# LCDController.net
KiCad netlist of a schematic drawn in EAGLE
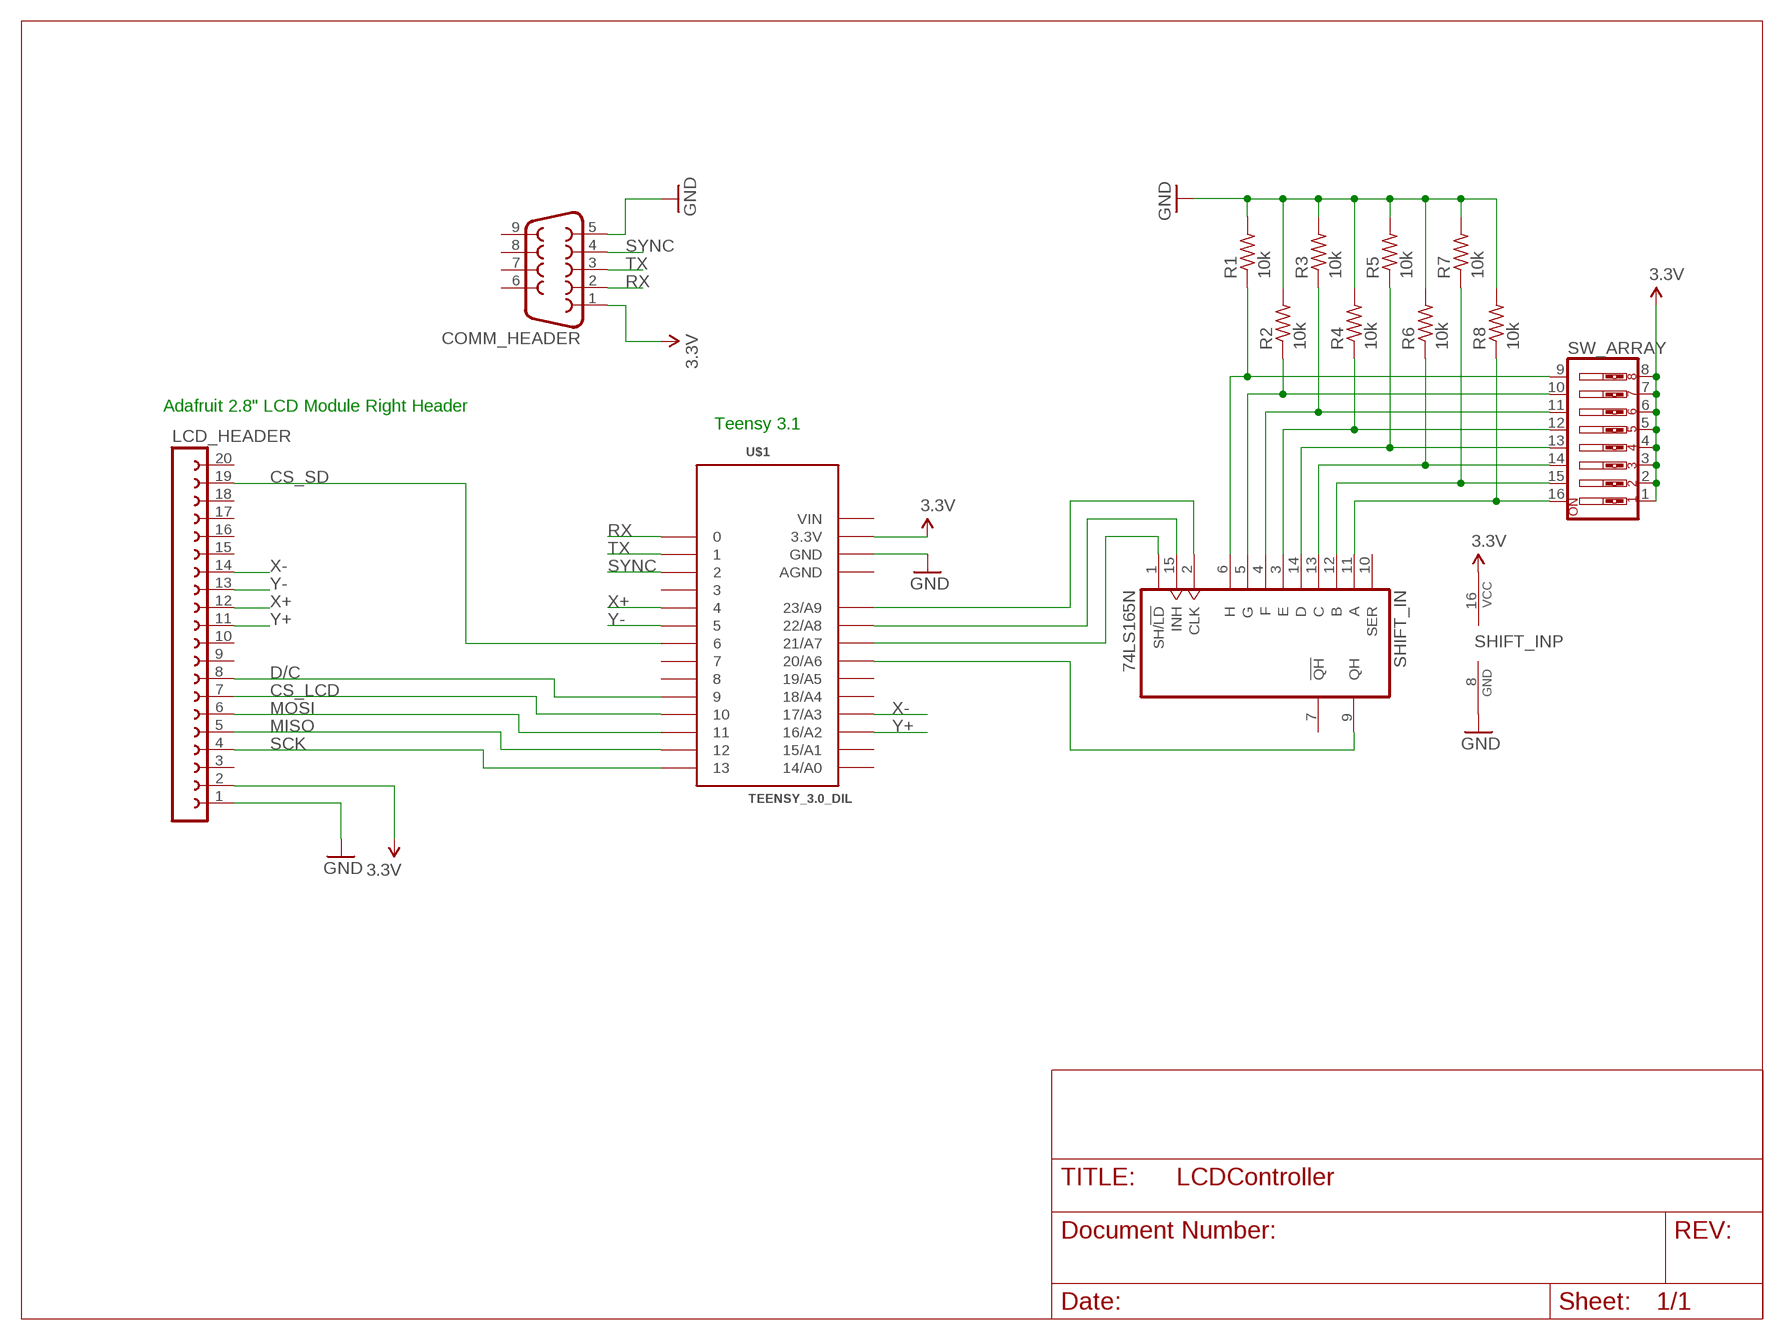
[diagram p0: schematic, sheet 1]

(export (version "E")
  (design (tool "Eeschema 10.0.6"))
  (components
    (comp (ref "COMM_HEADER")
      (value "F09VB")
      (footprint "eagle-import:F09VB")
      (libsource (lib "eagle-import") (part "F09VB"))
    )
    (comp (ref "LCD_HEADER")
      (value "FE20-1")
      (footprint "eagle-import:FE20")
      (libsource (lib "eagle-import") (part "FE20-1"))
    )
    (comp (ref "R1")
      (value "10k")
      (footprint "eagle-import:0204_5")
      (libsource (lib "eagle-import") (part "R-US_0204/5"))
    )
    (comp (ref "R2")
      (value "10k")
      (footprint "eagle-import:0204_5")
      (libsource (lib "eagle-import") (part "R-US_0204/5"))
    )
    (comp (ref "R3")
      (value "10k")
      (footprint "eagle-import:0204_5")
      (libsource (lib "eagle-import") (part "R-US_0204/5"))
    )
    (comp (ref "R4")
      (value "10k")
      (footprint "eagle-import:0204_5")
      (libsource (lib "eagle-import") (part "R-US_0204/5"))
    )
    (comp (ref "R5")
      (value "10k")
      (footprint "eagle-import:0204_5")
      (libsource (lib "eagle-import") (part "R-US_0204/5"))
    )
    (comp (ref "R6")
      (value "10k")
      (footprint "eagle-import:0204_5")
      (libsource (lib "eagle-import") (part "R-US_0204/5"))
    )
    (comp (ref "R7")
      (value "10k")
      (footprint "eagle-import:0204_5")
      (libsource (lib "eagle-import") (part "R-US_0204/5"))
    )
    (comp (ref "R8")
      (value "10k")
      (footprint "eagle-import:0204_5")
      (libsource (lib "eagle-import") (part "R-US_0204/5"))
    )
    (comp (ref "SHIFT_IN")
      (value "74LS165N")
      (footprint "eagle-import:DIL16")
      (libsource (lib "eagle-import") (part "74165NLS"))
    )
    (comp (ref "SW_ARRAY")
      (value "SW_DIP-8")
      (footprint "eagle-import:DIPSWITCH-08")
      (libsource (lib "eagle-import") (part "SW_DIP-8"))
    )
    (comp (ref "U$1")
      (value "TEENSY_3.0_DIL")
      (footprint "eagle-import:TEENSY3-DIL")
      (libsource (lib "eagle-import") (part "TEENSY_3.0_DIL"))
    )
  )
  (nets
    (net (code "1") (name "/AGND") (class "Default")
      (node (ref "U$1") (pin "AGND") (pinfunction "AGND_AGND") (pintype "power_in"))
    )
    (net (code "2") (name "/CS_LCD") (class "Default")
      (node (ref "LCD_HEADER") (pin "7") (pinfunction "7_7") (pintype "passive"))
      (node (ref "U$1") (pin "10") (pinfunction "10_10") (pintype "bidirectional"))
    )
    (net (code "3") (name "/CS_SD") (class "Default")
      (node (ref "LCD_HEADER") (pin "19") (pinfunction "19_19") (pintype "passive"))
      (node (ref "U$1") (pin "6") (pinfunction "6_6") (pintype "bidirectional"))
    )
    (net (code "4") (name "/D{slash}C") (class "Default")
      (node (ref "LCD_HEADER") (pin "8") (pinfunction "8_8") (pintype "passive"))
      (node (ref "U$1") (pin "9") (pinfunction "9_9") (pintype "bidirectional"))
    )
    (net (code "5") (name "/MISO") (class "Default")
      (node (ref "LCD_HEADER") (pin "5") (pinfunction "5_5") (pintype "passive"))
      (node (ref "U$1") (pin "12") (pinfunction "12_12") (pintype "bidirectional"))
    )
    (net (code "6") (name "/MOSI") (class "Default")
      (node (ref "LCD_HEADER") (pin "6") (pinfunction "6_6") (pintype "passive"))
      (node (ref "U$1") (pin "11") (pinfunction "11_11") (pintype "bidirectional"))
    )
    (net (code "7") (name "/RX") (class "Default")
      (node (ref "COMM_HEADER") (pin "2") (pinfunction "2_2") (pintype "passive"))
      (node (ref "U$1") (pin "0") (pinfunction "0_0") (pintype "bidirectional"))
    )
    (net (code "8") (name "/SCK") (class "Default")
      (node (ref "LCD_HEADER") (pin "4") (pinfunction "4_4") (pintype "passive"))
      (node (ref "U$1") (pin "13") (pinfunction "13_13") (pintype "bidirectional"))
    )
    (net (code "9") (name "/SYNC") (class "Default")
      (node (ref "COMM_HEADER") (pin "4") (pinfunction "4_4") (pintype "passive"))
      (node (ref "U$1") (pin "2") (pinfunction "2_2") (pintype "bidirectional"))
    )
    (net (code "10") (name "/TX") (class "Default")
      (node (ref "COMM_HEADER") (pin "3") (pinfunction "3_3") (pintype "passive"))
      (node (ref "U$1") (pin "1") (pinfunction "1_1") (pintype "bidirectional"))
    )
    (net (code "11") (name "/VIN") (class "Default")
      (node (ref "U$1") (pin "VIN") (pinfunction "VIN_VIN") (pintype "power_in"))
    )
    (net (code "12") (name "/X+") (class "Default")
      (node (ref "LCD_HEADER") (pin "12") (pinfunction "12_12") (pintype "passive"))
      (node (ref "U$1") (pin "4") (pinfunction "4_4") (pintype "bidirectional"))
    )
    (net (code "13") (name "/X-") (class "Default")
      (node (ref "LCD_HEADER") (pin "14") (pinfunction "14_14") (pintype "passive"))
      (node (ref "U$1") (pin "17/A3") (pinfunction "17/A3_17/A3") (pintype "bidirectional"))
    )
    (net (code "14") (name "/Y+") (class "Default")
      (node (ref "LCD_HEADER") (pin "11") (pinfunction "11_11") (pintype "passive"))
      (node (ref "U$1") (pin "16/A2") (pinfunction "16/A2_16/A2") (pintype "bidirectional"))
    )
    (net (code "15") (name "/Y-") (class "Default")
      (node (ref "LCD_HEADER") (pin "13") (pinfunction "13_13") (pintype "passive"))
      (node (ref "U$1") (pin "5") (pinfunction "5_5") (pintype "bidirectional"))
    )
    (net (code "16") (name "3.3V") (class "Default")
      (node (ref "COMM_HEADER") (pin "1") (pinfunction "1_1") (pintype "passive"))
      (node (ref "LCD_HEADER") (pin "2") (pinfunction "2_2") (pintype "passive"))
      (node (ref "SHIFT_IN") (pin "16") (pinfunction "VCC_16") (pintype "power_in"))
      (node (ref "SW_ARRAY") (pin "1") (pinfunction "1_1") (pintype "passive"))
      (node (ref "SW_ARRAY") (pin "2") (pinfunction "2_2") (pintype "passive"))
      (node (ref "SW_ARRAY") (pin "3") (pinfunction "3_3") (pintype "passive"))
      (node (ref "SW_ARRAY") (pin "4") (pinfunction "4_4") (pintype "passive"))
      (node (ref "SW_ARRAY") (pin "5") (pinfunction "5_5") (pintype "passive"))
      (node (ref "SW_ARRAY") (pin "6") (pinfunction "6_6") (pintype "passive"))
      (node (ref "SW_ARRAY") (pin "7") (pinfunction "7_7") (pintype "passive"))
      (node (ref "SW_ARRAY") (pin "8") (pinfunction "8_8") (pintype "passive"))
      (node (ref "U$1") (pin "3.3V") (pinfunction "3.3V_3.3V") (pintype "power_in"))
    )
    (net (code "17") (name "GND") (class "Default")
      (node (ref "COMM_HEADER") (pin "5") (pinfunction "5_5") (pintype "passive"))
      (node (ref "LCD_HEADER") (pin "1") (pinfunction "1_1") (pintype "passive"))
      (node (ref "R1") (pin "2") (pinfunction "2_2") (pintype "passive"))
      (node (ref "R2") (pin "2") (pinfunction "2_2") (pintype "passive"))
      (node (ref "R3") (pin "2") (pinfunction "2_2") (pintype "passive"))
      (node (ref "R4") (pin "2") (pinfunction "2_2") (pintype "passive"))
      (node (ref "R5") (pin "2") (pinfunction "2_2") (pintype "passive"))
      (node (ref "R6") (pin "2") (pinfunction "2_2") (pintype "passive"))
      (node (ref "R7") (pin "2") (pinfunction "2_2") (pintype "passive"))
      (node (ref "R8") (pin "2") (pinfunction "2_2") (pintype "passive"))
      (node (ref "SHIFT_IN") (pin "8") (pinfunction "GND_8") (pintype "power_in"))
      (node (ref "U$1") (pin "GND") (pinfunction "GND_GND") (pintype "power_in"))
    )
    (net (code "18") (name "Net-(SHIFT_INA-A)") (class "Default")
      (node (ref "R8") (pin "1") (pinfunction "1_1") (pintype "passive"))
      (node (ref "SHIFT_IN") (pin "11") (pinfunction "A_11") (pintype "input"))
      (node (ref "SW_ARRAY") (pin "16") (pinfunction "16_16") (pintype "passive"))
    )
    (net (code "19") (name "Net-(SHIFT_INA-B)") (class "Default")
      (node (ref "R7") (pin "1") (pinfunction "1_1") (pintype "passive"))
      (node (ref "SHIFT_IN") (pin "12") (pinfunction "B_12") (pintype "input"))
      (node (ref "SW_ARRAY") (pin "15") (pinfunction "15_15") (pintype "passive"))
    )
    (net (code "20") (name "Net-(SHIFT_INA-C)") (class "Default")
      (node (ref "R6") (pin "1") (pinfunction "1_1") (pintype "passive"))
      (node (ref "SHIFT_IN") (pin "13") (pinfunction "C_13") (pintype "input"))
      (node (ref "SW_ARRAY") (pin "14") (pinfunction "14_14") (pintype "passive"))
    )
    (net (code "21") (name "Net-(SHIFT_INA-CLK)") (class "Default")
      (node (ref "SHIFT_IN") (pin "2") (pinfunction "CLK_2") (pintype "input"))
      (node (ref "U$1") (pin "23/A9") (pinfunction "23/A9_23/A9") (pintype "bidirectional"))
    )
    (net (code "22") (name "Net-(SHIFT_INA-D)") (class "Default")
      (node (ref "R5") (pin "1") (pinfunction "1_1") (pintype "passive"))
      (node (ref "SHIFT_IN") (pin "14") (pinfunction "D_14") (pintype "input"))
      (node (ref "SW_ARRAY") (pin "13") (pinfunction "13_13") (pintype "passive"))
    )
    (net (code "23") (name "Net-(SHIFT_INA-E)") (class "Default")
      (node (ref "R4") (pin "1") (pinfunction "1_1") (pintype "passive"))
      (node (ref "SHIFT_IN") (pin "3") (pinfunction "E_3") (pintype "input"))
      (node (ref "SW_ARRAY") (pin "12") (pinfunction "12_12") (pintype "passive"))
    )
    (net (code "24") (name "Net-(SHIFT_INA-F)") (class "Default")
      (node (ref "R3") (pin "1") (pinfunction "1_1") (pintype "passive"))
      (node (ref "SHIFT_IN") (pin "4") (pinfunction "F_4") (pintype "input"))
      (node (ref "SW_ARRAY") (pin "11") (pinfunction "11_11") (pintype "passive"))
    )
    (net (code "25") (name "Net-(SHIFT_INA-G)") (class "Default")
      (node (ref "R2") (pin "1") (pinfunction "1_1") (pintype "passive"))
      (node (ref "SHIFT_IN") (pin "5") (pinfunction "G_5") (pintype "input"))
      (node (ref "SW_ARRAY") (pin "10") (pinfunction "10_10") (pintype "passive"))
    )
    (net (code "26") (name "Net-(SHIFT_INA-H)") (class "Default")
      (node (ref "R1") (pin "1") (pinfunction "1_1") (pintype "passive"))
      (node (ref "SHIFT_IN") (pin "6") (pinfunction "H_6") (pintype "input"))
      (node (ref "SW_ARRAY") (pin "9") (pinfunction "9_9") (pintype "passive"))
    )
    (net (code "27") (name "Net-(SHIFT_INA-INH)") (class "Default")
      (node (ref "SHIFT_IN") (pin "15") (pinfunction "INH_15") (pintype "input"))
      (node (ref "U$1") (pin "22/A8") (pinfunction "22/A8_22/A8") (pintype "bidirectional"))
    )
    (net (code "28") (name "Net-(SHIFT_INA-QH)") (class "Default")
      (node (ref "SHIFT_IN") (pin "9") (pinfunction "QH_9") (pintype "output"))
      (node (ref "U$1") (pin "20/A6") (pinfunction "20/A6_20/A6") (pintype "bidirectional"))
    )
    (net (code "29") (name "Net-(SHIFT_INA-SH{slash}~{LD})") (class "Default")
      (node (ref "SHIFT_IN") (pin "1") (pinfunction "SH/~{LD}_1") (pintype "input"))
      (node (ref "U$1") (pin "21/A7") (pinfunction "21/A7_21/A7") (pintype "bidirectional"))
    )
    (net (code "30") (name "unconnected-(COMM_HEADER-Pad6)") (class "Default")
      (node (ref "COMM_HEADER") (pin "6") (pinfunction "6_6") (pintype "passive"))
    )
    (net (code "31") (name "unconnected-(COMM_HEADER-Pad7)") (class "Default")
      (node (ref "COMM_HEADER") (pin "7") (pinfunction "7_7") (pintype "passive"))
    )
    (net (code "32") (name "unconnected-(COMM_HEADER-Pad8)") (class "Default")
      (node (ref "COMM_HEADER") (pin "8") (pinfunction "8_8") (pintype "passive"))
    )
    (net (code "33") (name "unconnected-(COMM_HEADER-Pad9)") (class "Default")
      (node (ref "COMM_HEADER") (pin "9") (pinfunction "9_9") (pintype "passive"))
    )
    (net (code "34") (name "unconnected-(LCD_HEADER-Pad3)") (class "Default")
      (node (ref "LCD_HEADER") (pin "3") (pinfunction "3_3") (pintype "passive"))
    )
    (net (code "35") (name "unconnected-(LCD_HEADER-Pad9)") (class "Default")
      (node (ref "LCD_HEADER") (pin "9") (pinfunction "9_9") (pintype "passive"))
    )
    (net (code "36") (name "unconnected-(LCD_HEADER-Pad10)") (class "Default")
      (node (ref "LCD_HEADER") (pin "10") (pinfunction "10_10") (pintype "passive"))
    )
    (net (code "37") (name "unconnected-(LCD_HEADER-Pad15)") (class "Default")
      (node (ref "LCD_HEADER") (pin "15") (pinfunction "15_15") (pintype "passive"))
    )
    (net (code "38") (name "unconnected-(LCD_HEADER-Pad16)") (class "Default")
      (node (ref "LCD_HEADER") (pin "16") (pinfunction "16_16") (pintype "passive"))
    )
    (net (code "39") (name "unconnected-(LCD_HEADER-Pad17)") (class "Default")
      (node (ref "LCD_HEADER") (pin "17") (pinfunction "17_17") (pintype "passive"))
    )
    (net (code "40") (name "unconnected-(LCD_HEADER-Pad18)") (class "Default")
      (node (ref "LCD_HEADER") (pin "18") (pinfunction "18_18") (pintype "passive"))
    )
    (net (code "41") (name "unconnected-(LCD_HEADER-Pad20)") (class "Default")
      (node (ref "LCD_HEADER") (pin "20") (pinfunction "20_20") (pintype "passive"))
    )
    (net (code "42") (name "unconnected-(SHIFT_INA-SER-Pad10)") (class "Default")
      (node (ref "SHIFT_IN") (pin "10") (pinfunction "SER_10") (pintype "input"))
    )
    (net (code "43") (name "unconnected-(SHIFT_INA-~{QH}-Pad7)") (class "Default")
      (node (ref "SHIFT_IN") (pin "7") (pinfunction "~{QH}_7") (pintype "output"))
    )
    (net (code "44") (name "unconnected-(U$1-Pad3)") (class "Default")
      (node (ref "U$1") (pin "3") (pinfunction "3_3") (pintype "bidirectional"))
    )
    (net (code "45") (name "unconnected-(U$1-Pad7)") (class "Default")
      (node (ref "U$1") (pin "7") (pinfunction "7_7") (pintype "bidirectional"))
    )
    (net (code "46") (name "unconnected-(U$1-Pad8)") (class "Default")
      (node (ref "U$1") (pin "8") (pinfunction "8_8") (pintype "bidirectional"))
    )
    (net (code "47") (name "unconnected-(U$1-Pad14{slash}A0)") (class "Default")
      (node (ref "U$1") (pin "14/A0") (pinfunction "14/A0_14/A0") (pintype "bidirectional"))
    )
    (net (code "48") (name "unconnected-(U$1-Pad15{slash}A1)") (class "Default")
      (node (ref "U$1") (pin "15/A1") (pinfunction "15/A1_15/A1") (pintype "bidirectional"))
    )
    (net (code "49") (name "unconnected-(U$1-Pad18{slash}A4)") (class "Default")
      (node (ref "U$1") (pin "18/A4") (pinfunction "18/A4_18/A4") (pintype "bidirectional"))
    )
    (net (code "50") (name "unconnected-(U$1-Pad19{slash}A5)") (class "Default")
      (node (ref "U$1") (pin "19/A5") (pinfunction "19/A5_19/A5") (pintype "bidirectional"))
    )
  )
)
